# Embedded_System_Top.net
KiCad netlist of a schematic drawn in Altium Designer
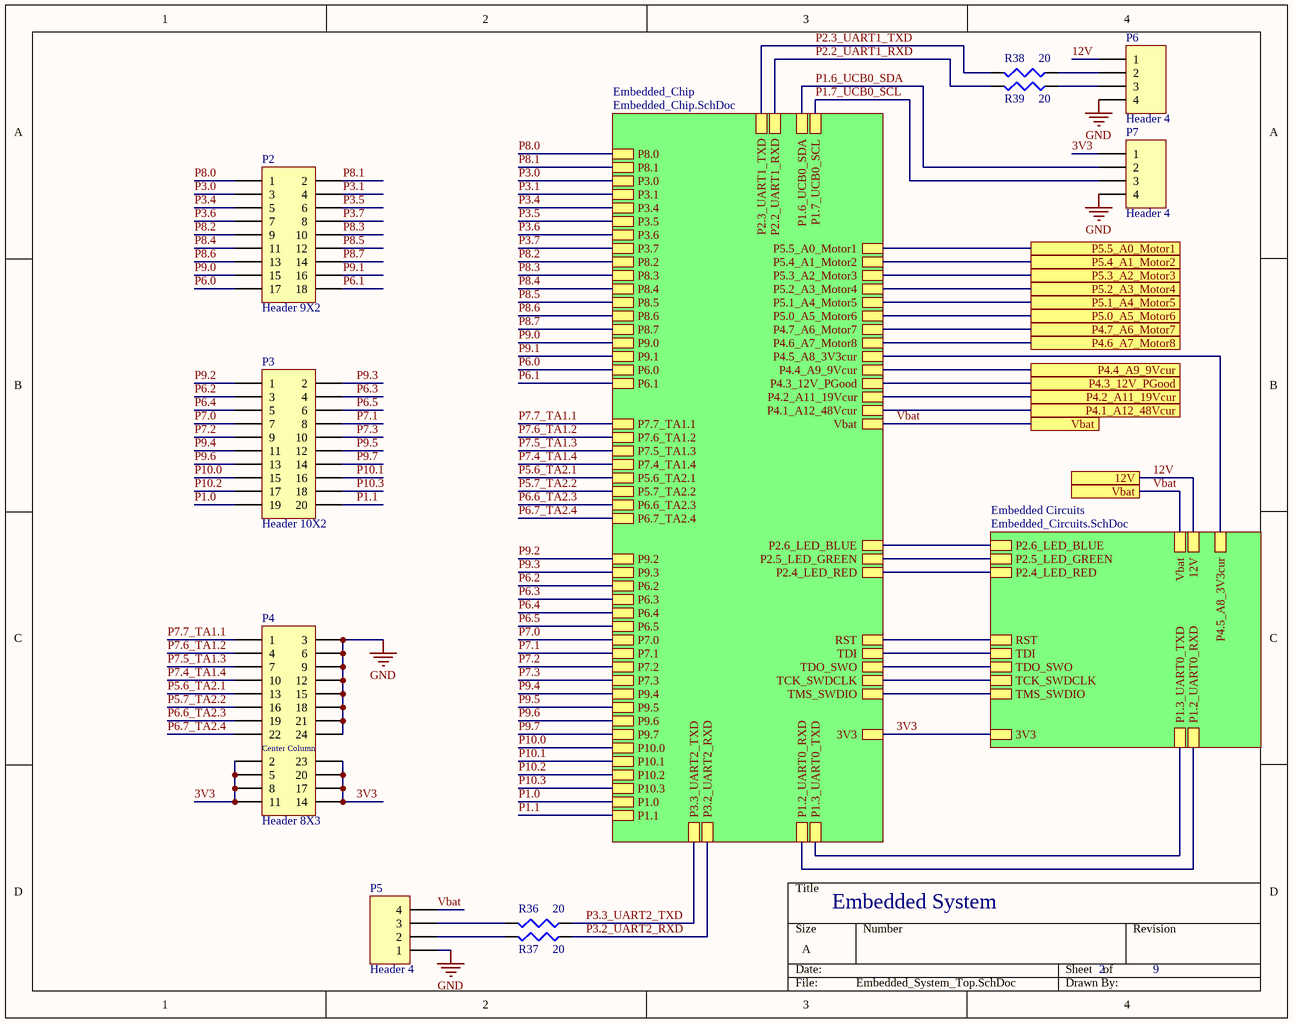
[diagram p0: Embedded_System_Top.SchDoc]

(export (version "E")
  (design (tool "Eeschema 10.0.6"))
  (components
    (comp (ref "P2")
      (value "Header 9X2")
      (footprint "Header 2x9")
      (description "Header, 9-Pin, Dual row")
      (fields (field (name "PUBLISHER") "Altium Limited"))
      (libsource (lib "Miscellaneous Connectors") (part "Header 9X2"))
    )
    (comp (ref "P3")
      (value "Header 10X2")
      (footprint "Header 2x10")
      (description "Header, 10-Pin, Dual row")
      (fields (field (name "PUBLISHER") "Altium Limited"))
      (libsource (lib "Miscellaneous Connectors") (part "Header 10X2"))
    )
    (comp (ref "P4")
      (value "Header 8X3")
      (footprint "Header 8X3")
      (description "Connector Header Through Hole 24 position 0.079\" (2.00mm)")
      (libsource (lib "Power_Embedded_Board_Library") (part "Header 8X3 (2mm)"))
    )
    (comp (ref "P5")
      (value "Header 4")
      (footprint "Header 1x4")
      (description "Header, 4-Pin")
      (fields (field (name "PUBLISHER") "Altium Limited"))
      (libsource (lib "Miscellaneous Connectors") (part "Header 4"))
    )
    (comp (ref "P6")
      (value "Header 4")
      (footprint "Header 1x4")
      (description "Header, 4-Pin")
      (fields (field (name "PUBLISHER") "Altium Limited"))
      (libsource (lib "") (part "Header 4_1"))
    )
    (comp (ref "P7")
      (value "Header 4")
      (footprint "Header 1x4")
      (description "Header, 4-Pin")
      (fields (field (name "PUBLISHER") "Altium Limited"))
      (libsource (lib "") (part "Header 4_1"))
    )
    (comp (ref "R36")
      (value "20")
      (footprint "J1-0603")
      (description "Resistor")
      (fields (field (name "Comment") "Res3") (field (name "PUBLISHER") "Altium Limited"))
      (libsource (lib "Miscellaneous Devices") (part "Res3"))
    )
    (comp (ref "R37")
      (value "20")
      (footprint "J1-0603")
      (description "Resistor")
      (fields (field (name "Comment") "Res3") (field (name "PUBLISHER") "Altium Limited"))
      (libsource (lib "Miscellaneous Devices") (part "Res3"))
    )
    (comp (ref "R38")
      (value "20")
      (footprint "J1-0603")
      (description "Resistor")
      (fields (field (name "Comment") "Res3") (field (name "PUBLISHER") "Altium Limited"))
      (libsource (lib "Miscellaneous Devices") (part "Res3"))
    )
    (comp (ref "R39")
      (value "20")
      (footprint "J1-0603")
      (description "Resistor")
      (fields (field (name "Comment") "Res3") (field (name "PUBLISHER") "Altium Limited"))
      (libsource (lib "Miscellaneous Devices") (part "Res3"))
    )
  )
  (nets
    (net (code "1") (name "/3V3") (class "Default")
      (node (ref "P4") (pin "11") (pinfunction "11_11") (pintype "passive"))
      (node (ref "P4") (pin "14") (pinfunction "14_14") (pintype "passive"))
      (node (ref "P4") (pin "17") (pinfunction "17_17") (pintype "passive"))
      (node (ref "P4") (pin "2") (pinfunction "2_2") (pintype "passive"))
      (node (ref "P4") (pin "20") (pinfunction "20_20") (pintype "passive"))
      (node (ref "P4") (pin "23") (pinfunction "23_23") (pintype "passive"))
      (node (ref "P4") (pin "5") (pinfunction "5_5") (pintype "passive"))
      (node (ref "P4") (pin "8") (pinfunction "8_8") (pintype "passive"))
      (node (ref "P7") (pin "1") (pinfunction "1_1") (pintype "passive"))
    )
    (net (code "2") (name "/12V") (class "Default")
      (node (ref "P6") (pin "1") (pinfunction "1_1") (pintype "passive"))
    )
    (net (code "3") (name "/P1.0") (class "Default")
      (node (ref "P3") (pin "19") (pinfunction "19_19") (pintype "passive"))
    )
    (net (code "4") (name "/P1.1") (class "Default")
      (node (ref "P3") (pin "20") (pinfunction "20_20") (pintype "passive"))
    )
    (net (code "7") (name "/P1.6_UCB0_SDA") (class "Default")
      (node (ref "P7") (pin "2") (pinfunction "2_2") (pintype "passive"))
    )
    (net (code "8") (name "/P1.7_UCB0_SCL") (class "Default")
      (node (ref "P7") (pin "3") (pinfunction "3_3") (pintype "passive"))
    )
    (net (code "9") (name "/P2.2_UART1_RXD") (class "Default")
      (node (ref "R39") (pin "2") (pinfunction "2_2") (pintype "passive"))
    )
    (net (code "10") (name "/P2.3_UART1_TXD") (class "Default")
      (node (ref "R38") (pin "2") (pinfunction "2_2") (pintype "passive"))
    )
    (net (code "14") (name "/P3.0") (class "Default")
      (node (ref "P2") (pin "3") (pinfunction "3_3") (pintype "passive"))
    )
    (net (code "15") (name "/P3.1") (class "Default")
      (node (ref "P2") (pin "4") (pinfunction "4_4") (pintype "passive"))
    )
    (net (code "16") (name "/P3.2_UART2_RXD") (class "Default")
      (node (ref "R37") (pin "1") (pinfunction "1_1") (pintype "passive"))
    )
    (net (code "17") (name "/P3.3_UART2_TXD") (class "Default")
      (node (ref "R36") (pin "1") (pinfunction "1_1") (pintype "passive"))
    )
    (net (code "18") (name "/P3.4") (class "Default")
      (node (ref "P2") (pin "5") (pinfunction "5_5") (pintype "passive"))
    )
    (net (code "19") (name "/P3.5") (class "Default")
      (node (ref "P2") (pin "6") (pinfunction "6_6") (pintype "passive"))
    )
    (net (code "20") (name "/P3.6") (class "Default")
      (node (ref "P2") (pin "7") (pinfunction "7_7") (pintype "passive"))
    )
    (net (code "21") (name "/P3.7") (class "Default")
      (node (ref "P2") (pin "8") (pinfunction "8_8") (pintype "passive"))
    )
    (net (code "35") (name "/P5.6_TA2.1") (class "Default")
      (node (ref "P4") (pin "13") (pinfunction "13_13") (pintype "passive"))
    )
    (net (code "36") (name "/P5.7_TA2.2") (class "Default")
      (node (ref "P4") (pin "16") (pinfunction "16_16") (pintype "passive"))
    )
    (net (code "37") (name "/P6.0") (class "Default")
      (node (ref "P2") (pin "17") (pinfunction "17_17") (pintype "passive"))
    )
    (net (code "38") (name "/P6.1") (class "Default")
      (node (ref "P2") (pin "18") (pinfunction "18_18") (pintype "passive"))
    )
    (net (code "39") (name "/P6.2") (class "Default")
      (node (ref "P3") (pin "3") (pinfunction "3_3") (pintype "passive"))
    )
    (net (code "40") (name "/P6.3") (class "Default")
      (node (ref "P3") (pin "4") (pinfunction "4_4") (pintype "passive"))
    )
    (net (code "41") (name "/P6.4") (class "Default")
      (node (ref "P3") (pin "5") (pinfunction "5_5") (pintype "passive"))
    )
    (net (code "42") (name "/P6.5") (class "Default")
      (node (ref "P3") (pin "6") (pinfunction "6_6") (pintype "passive"))
    )
    (net (code "43") (name "/P6.6_TA2.3") (class "Default")
      (node (ref "P4") (pin "19") (pinfunction "19_19") (pintype "passive"))
    )
    (net (code "44") (name "/P6.7_TA2.4") (class "Default")
      (node (ref "P4") (pin "22") (pinfunction "22_22") (pintype "passive"))
    )
    (net (code "45") (name "/P7.0") (class "Default")
      (node (ref "P3") (pin "7") (pinfunction "7_7") (pintype "passive"))
    )
    (net (code "46") (name "/P7.1") (class "Default")
      (node (ref "P3") (pin "8") (pinfunction "8_8") (pintype "passive"))
    )
    (net (code "47") (name "/P7.2") (class "Default")
      (node (ref "P3") (pin "9") (pinfunction "9_9") (pintype "passive"))
    )
    (net (code "48") (name "/P7.3") (class "Default")
      (node (ref "P3") (pin "10") (pinfunction "10_10") (pintype "passive"))
    )
    (net (code "49") (name "/P7.4_TA1.4") (class "Default")
      (node (ref "P4") (pin "10") (pinfunction "10_10") (pintype "passive"))
    )
    (net (code "50") (name "/P7.5_TA1.3") (class "Default")
      (node (ref "P4") (pin "7") (pinfunction "7_7") (pintype "passive"))
    )
    (net (code "51") (name "/P7.6_TA1.2") (class "Default")
      (node (ref "P4") (pin "4") (pinfunction "4_4") (pintype "passive"))
    )
    (net (code "52") (name "/P7.7_TA1.1") (class "Default")
      (node (ref "P4") (pin "1") (pinfunction "1_1") (pintype "passive"))
    )
    (net (code "53") (name "/P8.0") (class "Default")
      (node (ref "P2") (pin "1") (pinfunction "1_1") (pintype "passive"))
    )
    (net (code "54") (name "/P8.1") (class "Default")
      (node (ref "P2") (pin "2") (pinfunction "2_2") (pintype "passive"))
    )
    (net (code "55") (name "/P8.2") (class "Default")
      (node (ref "P2") (pin "9") (pinfunction "9_9") (pintype "passive"))
    )
    (net (code "56") (name "/P8.3") (class "Default")
      (node (ref "P2") (pin "10") (pinfunction "10_10") (pintype "passive"))
    )
    (net (code "57") (name "/P8.4") (class "Default")
      (node (ref "P2") (pin "11") (pinfunction "11_11") (pintype "passive"))
    )
    (net (code "58") (name "/P8.5") (class "Default")
      (node (ref "P2") (pin "12") (pinfunction "12_12") (pintype "passive"))
    )
    (net (code "59") (name "/P8.6") (class "Default")
      (node (ref "P2") (pin "13") (pinfunction "13_13") (pintype "passive"))
    )
    (net (code "60") (name "/P8.7") (class "Default")
      (node (ref "P2") (pin "14") (pinfunction "14_14") (pintype "passive"))
    )
    (net (code "61") (name "/P9.0") (class "Default")
      (node (ref "P2") (pin "15") (pinfunction "15_15") (pintype "passive"))
    )
    (net (code "62") (name "/P9.1") (class "Default")
      (node (ref "P2") (pin "16") (pinfunction "16_16") (pintype "passive"))
    )
    (net (code "63") (name "/P9.2") (class "Default")
      (node (ref "P3") (pin "1") (pinfunction "1_1") (pintype "passive"))
    )
    (net (code "64") (name "/P9.3") (class "Default")
      (node (ref "P3") (pin "2") (pinfunction "2_2") (pintype "passive"))
    )
    (net (code "65") (name "/P9.4") (class "Default")
      (node (ref "P3") (pin "11") (pinfunction "11_11") (pintype "passive"))
    )
    (net (code "66") (name "/P9.5") (class "Default")
      (node (ref "P3") (pin "12") (pinfunction "12_12") (pintype "passive"))
    )
    (net (code "67") (name "/P9.6") (class "Default")
      (node (ref "P3") (pin "13") (pinfunction "13_13") (pintype "passive"))
    )
    (net (code "68") (name "/P9.7") (class "Default")
      (node (ref "P3") (pin "14") (pinfunction "14_14") (pintype "passive"))
    )
    (net (code "69") (name "/P10.0") (class "Default")
      (node (ref "P3") (pin "15") (pinfunction "15_15") (pintype "passive"))
    )
    (net (code "70") (name "/P10.1") (class "Default")
      (node (ref "P3") (pin "16") (pinfunction "16_16") (pintype "passive"))
    )
    (net (code "71") (name "/P10.2") (class "Default")
      (node (ref "P3") (pin "17") (pinfunction "17_17") (pintype "passive"))
    )
    (net (code "72") (name "/P10.3") (class "Default")
      (node (ref "P3") (pin "18") (pinfunction "18_18") (pintype "passive"))
    )
    (net (code "78") (name "/Vbat") (class "Default")
      (node (ref "P5") (pin "4") (pinfunction "4_4") (pintype "passive"))
    )
    (net (code "79") (name "GND") (class "Default")
      (node (ref "P4") (pin "12") (pinfunction "12_12") (pintype "passive"))
      (node (ref "P4") (pin "15") (pinfunction "15_15") (pintype "passive"))
      (node (ref "P4") (pin "18") (pinfunction "18_18") (pintype "passive"))
      (node (ref "P4") (pin "21") (pinfunction "21_21") (pintype "passive"))
      (node (ref "P4") (pin "24") (pinfunction "24_24") (pintype "passive"))
      (node (ref "P4") (pin "3") (pinfunction "3_3") (pintype "passive"))
      (node (ref "P4") (pin "6") (pinfunction "6_6") (pintype "passive"))
      (node (ref "P4") (pin "9") (pinfunction "9_9") (pintype "passive"))
      (node (ref "P5") (pin "1") (pinfunction "1_1") (pintype "passive"))
      (node (ref "P6") (pin "4") (pinfunction "4_4") (pintype "passive"))
      (node (ref "P7") (pin "4") (pinfunction "4_4") (pintype "passive"))
    )
    (net (code "80") (name "Net-(P5-Pad2)") (class "Default")
      (node (ref "P5") (pin "2") (pinfunction "2_2") (pintype "passive"))
      (node (ref "R37") (pin "2") (pinfunction "2_2") (pintype "passive"))
    )
    (net (code "81") (name "Net-(P5-Pad3)") (class "Default")
      (node (ref "P5") (pin "3") (pinfunction "3_3") (pintype "passive"))
      (node (ref "R36") (pin "2") (pinfunction "2_2") (pintype "passive"))
    )
    (net (code "82") (name "Net-(P6-Pad2)") (class "Default")
      (node (ref "P6") (pin "2") (pinfunction "2_2") (pintype "passive"))
      (node (ref "R38") (pin "1") (pinfunction "1_1") (pintype "passive"))
    )
    (net (code "83") (name "Net-(P6-Pad3)") (class "Default")
      (node (ref "P6") (pin "3") (pinfunction "3_3") (pintype "passive"))
      (node (ref "R39") (pin "1") (pinfunction "1_1") (pintype "passive"))
    )
  )
)
